# deska.net
KiCad netlist of a schematic drawn in EAGLE
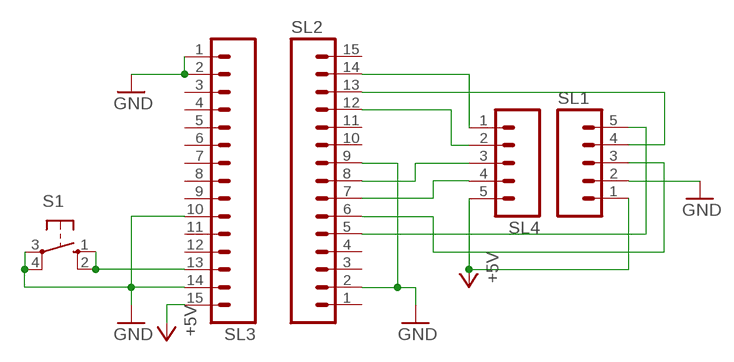
[diagram p0: schematic, sheet 1]

(export (version "E")
  (design (tool "Eeschema 10.0.6"))
  (components
    (comp (ref "S1")
      (value "10-XX")
      (footprint "eagle-import:B3F-10XX")
      (fields (field (name "MPN") "B3F-1000"))
      (libsource (lib "eagle-import") (part "10-XX"))
    )
    (comp (ref "SL1")
      (value "MA05")
      (footprint "eagle-import:05PA")
      (libsource (lib "eagle-import") (part "MA05"))
    )
    (comp (ref "SL2")
      (value "MA15")
      (footprint "eagle-import:15PA")
      (libsource (lib "eagle-import") (part "MA15"))
    )
    (comp (ref "SL3")
      (value "MA15")
      (footprint "eagle-import:15PA")
      (libsource (lib "eagle-import") (part "MA15"))
    )
    (comp (ref "SL4")
      (value "MA05")
      (footprint "eagle-import:05PA")
      (libsource (lib "eagle-import") (part "MA05"))
    )
  )
  (nets
    (net (code "1") (name "+5V") (class "Default")
      (node (ref "SL1") (pin "1") (pinfunction "1_1") (pintype "passive"))
      (node (ref "SL3") (pin "15") (pinfunction "15_15") (pintype "passive"))
      (node (ref "SL4") (pin "5") (pinfunction "5_5") (pintype "passive"))
    )
    (net (code "2") (name "GND") (class "Default")
      (node (ref "S1") (pin "3") (pinfunction "P_3") (pintype "passive"))
      (node (ref "S1") (pin "4") (pinfunction "P1_4") (pintype "passive"))
      (node (ref "SL1") (pin "2") (pinfunction "2_2") (pintype "passive"))
      (node (ref "SL2") (pin "2") (pinfunction "2_2") (pintype "passive"))
      (node (ref "SL2") (pin "9") (pinfunction "9_9") (pintype "passive"))
      (node (ref "SL3") (pin "1") (pinfunction "1_1") (pintype "passive"))
      (node (ref "SL3") (pin "10") (pinfunction "10_10") (pintype "passive"))
      (node (ref "SL3") (pin "14") (pinfunction "14_14") (pintype "passive"))
      (node (ref "SL3") (pin "2") (pinfunction "2_2") (pintype "passive"))
    )
    (net (code "3") (name "Net-(S1-S)") (class "Default")
      (node (ref "S1") (pin "1") (pinfunction "S_1") (pintype "passive"))
      (node (ref "S1") (pin "2") (pinfunction "S1_2") (pintype "passive"))
      (node (ref "SL3") (pin "13") (pinfunction "13_13") (pintype "passive"))
    )
    (net (code "4") (name "Net-(SL1-Pad3)") (class "Default")
      (node (ref "SL1") (pin "3") (pinfunction "3_3") (pintype "passive"))
      (node (ref "SL2") (pin "6") (pinfunction "6_6") (pintype "passive"))
    )
    (net (code "5") (name "Net-(SL1-Pad4)") (class "Default")
      (node (ref "SL1") (pin "4") (pinfunction "4_4") (pintype "passive"))
      (node (ref "SL2") (pin "13") (pinfunction "13_13") (pintype "passive"))
    )
    (net (code "6") (name "Net-(SL1-Pad5)") (class "Default")
      (node (ref "SL1") (pin "5") (pinfunction "5_5") (pintype "passive"))
      (node (ref "SL2") (pin "5") (pinfunction "5_5") (pintype "passive"))
    )
    (net (code "7") (name "Net-(SL2-Pad7)") (class "Default")
      (node (ref "SL2") (pin "7") (pinfunction "7_7") (pintype "passive"))
      (node (ref "SL4") (pin "4") (pinfunction "4_4") (pintype "passive"))
    )
    (net (code "8") (name "Net-(SL2-Pad8)") (class "Default")
      (node (ref "SL2") (pin "8") (pinfunction "8_8") (pintype "passive"))
      (node (ref "SL4") (pin "3") (pinfunction "3_3") (pintype "passive"))
    )
    (net (code "9") (name "Net-(SL2-Pad12)") (class "Default")
      (node (ref "SL2") (pin "12") (pinfunction "12_12") (pintype "passive"))
      (node (ref "SL4") (pin "2") (pinfunction "2_2") (pintype "passive"))
    )
    (net (code "10") (name "Net-(SL2-Pad14)") (class "Default")
      (node (ref "SL2") (pin "14") (pinfunction "14_14") (pintype "passive"))
      (node (ref "SL4") (pin "1") (pinfunction "1_1") (pintype "passive"))
    )
    (net (code "11") (name "unconnected-(SL2-Pad1)") (class "Default")
      (node (ref "SL2") (pin "1") (pinfunction "1_1") (pintype "passive"))
    )
    (net (code "12") (name "unconnected-(SL2-Pad3)") (class "Default")
      (node (ref "SL2") (pin "3") (pinfunction "3_3") (pintype "passive"))
    )
    (net (code "13") (name "unconnected-(SL2-Pad4)") (class "Default")
      (node (ref "SL2") (pin "4") (pinfunction "4_4") (pintype "passive"))
    )
    (net (code "14") (name "unconnected-(SL2-Pad10)") (class "Default")
      (node (ref "SL2") (pin "10") (pinfunction "10_10") (pintype "passive"))
    )
    (net (code "15") (name "unconnected-(SL2-Pad11)") (class "Default")
      (node (ref "SL2") (pin "11") (pinfunction "11_11") (pintype "passive"))
    )
    (net (code "16") (name "unconnected-(SL2-Pad15)") (class "Default")
      (node (ref "SL2") (pin "15") (pinfunction "15_15") (pintype "passive"))
    )
    (net (code "17") (name "unconnected-(SL3-Pad3)") (class "Default")
      (node (ref "SL3") (pin "3") (pinfunction "3_3") (pintype "passive"))
    )
    (net (code "18") (name "unconnected-(SL3-Pad4)") (class "Default")
      (node (ref "SL3") (pin "4") (pinfunction "4_4") (pintype "passive"))
    )
    (net (code "19") (name "unconnected-(SL3-Pad5)") (class "Default")
      (node (ref "SL3") (pin "5") (pinfunction "5_5") (pintype "passive"))
    )
    (net (code "20") (name "unconnected-(SL3-Pad6)") (class "Default")
      (node (ref "SL3") (pin "6") (pinfunction "6_6") (pintype "passive"))
    )
    (net (code "21") (name "unconnected-(SL3-Pad7)") (class "Default")
      (node (ref "SL3") (pin "7") (pinfunction "7_7") (pintype "passive"))
    )
    (net (code "22") (name "unconnected-(SL3-Pad8)") (class "Default")
      (node (ref "SL3") (pin "8") (pinfunction "8_8") (pintype "passive"))
    )
    (net (code "23") (name "unconnected-(SL3-Pad9)") (class "Default")
      (node (ref "SL3") (pin "9") (pinfunction "9_9") (pintype "passive"))
    )
    (net (code "24") (name "unconnected-(SL3-Pad11)") (class "Default")
      (node (ref "SL3") (pin "11") (pinfunction "11_11") (pintype "passive"))
    )
    (net (code "25") (name "unconnected-(SL3-Pad12)") (class "Default")
      (node (ref "SL3") (pin "12") (pinfunction "12_12") (pintype "passive"))
    )
  )
)
